# um232r.net
KiCad netlist of a schematic drawn in Altium Designer
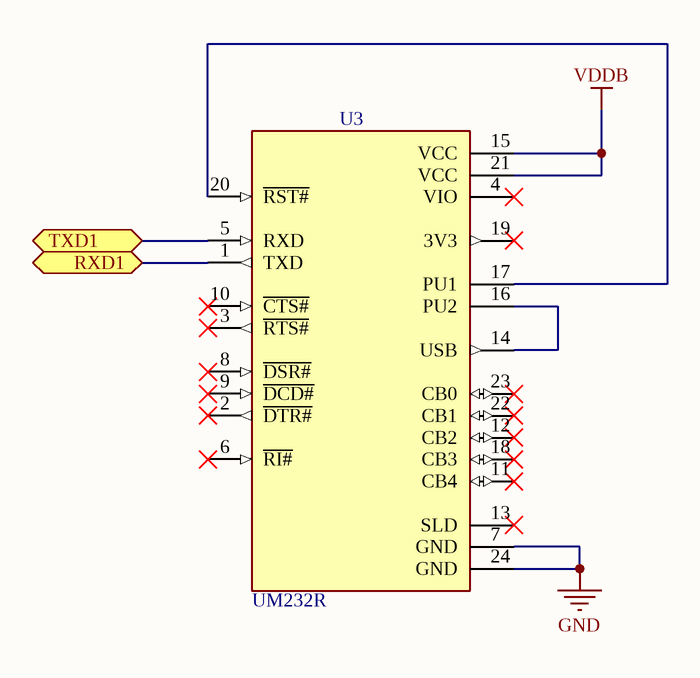
[diagram p0: um232r.SchDoc]

(export (version "E")
  (design (tool "Eeschema 10.0.6"))
  (components
    (comp (ref "U3")
      (value "UM232R")
      (footprint "MODULE_UM232R")
      (description "FT232R USB 2.0 to UART (RS232) Bridge Interface Evaluation Board")
      (fields (field (name "MF") "FTDI,"))
      (libsource (lib "UM232R") (part "UM232R"))
    )
  )
  (nets
    (net (code "1") (name "/RXD1") (class "Default")
      (node (ref "U3") (pin "1") (pinfunction "TXD_1") (pintype "output"))
    )
    (net (code "2") (name "/TXD1") (class "Default")
      (node (ref "U3") (pin "5") (pinfunction "RXD_5") (pintype "input"))
    )
    (net (code "3") (name "GND") (class "Default")
      (node (ref "U3") (pin "24") (pinfunction "GND_24") (pintype "power_in"))
      (node (ref "U3") (pin "7") (pinfunction "GND_7") (pintype "power_in"))
    )
    (net (code "4") (name "Net-(U3-PU1)") (class "Default")
      (node (ref "U3") (pin "17") (pinfunction "PU1_17") (pintype "passive"))
      (node (ref "U3") (pin "20") (pinfunction "~{RST#}_20") (pintype "input"))
    )
    (net (code "5") (name "Net-(U3-PU2)") (class "Default")
      (node (ref "U3") (pin "14") (pinfunction "USB_14") (pintype "output"))
      (node (ref "U3") (pin "16") (pinfunction "PU2_16") (pintype "passive"))
    )
    (net (code "6") (name "VDDB") (class "Default")
      (node (ref "U3") (pin "15") (pinfunction "VCC_15") (pintype "power_in"))
      (node (ref "U3") (pin "21") (pinfunction "VCC_21") (pintype "power_in"))
    )
    (net (code "7") (name "unconnected-(U3-3V3-Pad19)") (class "Default")
      (node (ref "U3") (pin "19") (pinfunction "3V3_19") (pintype "output+no_connect"))
    )
    (net (code "8") (name "unconnected-(U3-CB0-Pad23)") (class "Default")
      (node (ref "U3") (pin "23") (pinfunction "CB0_23") (pintype "bidirectional+no_connect"))
    )
    (net (code "9") (name "unconnected-(U3-CB1-Pad22)") (class "Default")
      (node (ref "U3") (pin "22") (pinfunction "CB1_22") (pintype "bidirectional+no_connect"))
    )
    (net (code "10") (name "unconnected-(U3-CB2-Pad12)") (class "Default")
      (node (ref "U3") (pin "12") (pinfunction "CB2_12") (pintype "bidirectional+no_connect"))
    )
    (net (code "11") (name "unconnected-(U3-CB3-Pad18)") (class "Default")
      (node (ref "U3") (pin "18") (pinfunction "CB3_18") (pintype "bidirectional+no_connect"))
    )
    (net (code "12") (name "unconnected-(U3-CB4-Pad11)") (class "Default")
      (node (ref "U3") (pin "11") (pinfunction "CB4_11") (pintype "bidirectional+no_connect"))
    )
    (net (code "13") (name "unconnected-(U3-SLD-Pad13)") (class "Default")
      (node (ref "U3") (pin "13") (pinfunction "SLD_13") (pintype "power_in+no_connect"))
    )
    (net (code "14") (name "unconnected-(U3-VIO-Pad4)") (class "Default")
      (node (ref "U3") (pin "4") (pinfunction "VIO_4") (pintype "power_in+no_connect"))
    )
    (net (code "15") (name "unconnected-(U3-~{CTS#}-Pad10)") (class "Default")
      (node (ref "U3") (pin "10") (pinfunction "~{CTS#}_10") (pintype "input+no_connect"))
    )
    (net (code "16") (name "unconnected-(U3-~{DCD#}-Pad9)") (class "Default")
      (node (ref "U3") (pin "9") (pinfunction "~{DCD#}_9") (pintype "input+no_connect"))
    )
    (net (code "17") (name "unconnected-(U3-~{DSR#}-Pad8)") (class "Default")
      (node (ref "U3") (pin "8") (pinfunction "~{DSR#}_8") (pintype "input+no_connect"))
    )
    (net (code "18") (name "unconnected-(U3-~{DTR#}-Pad2)") (class "Default")
      (node (ref "U3") (pin "2") (pinfunction "~{DTR#}_2") (pintype "output+no_connect"))
    )
    (net (code "19") (name "unconnected-(U3-~{RI#}-Pad6)") (class "Default")
      (node (ref "U3") (pin "6") (pinfunction "~{RI#}_6") (pintype "input+no_connect"))
    )
    (net (code "20") (name "unconnected-(U3-~{RTS#}-Pad3)") (class "Default")
      (node (ref "U3") (pin "3") (pinfunction "~{RTS#}_3") (pintype "output+no_connect"))
    )
  )
)
